# small_laser_supply.net
KiCad netlist of a schematic drawn in EAGLE
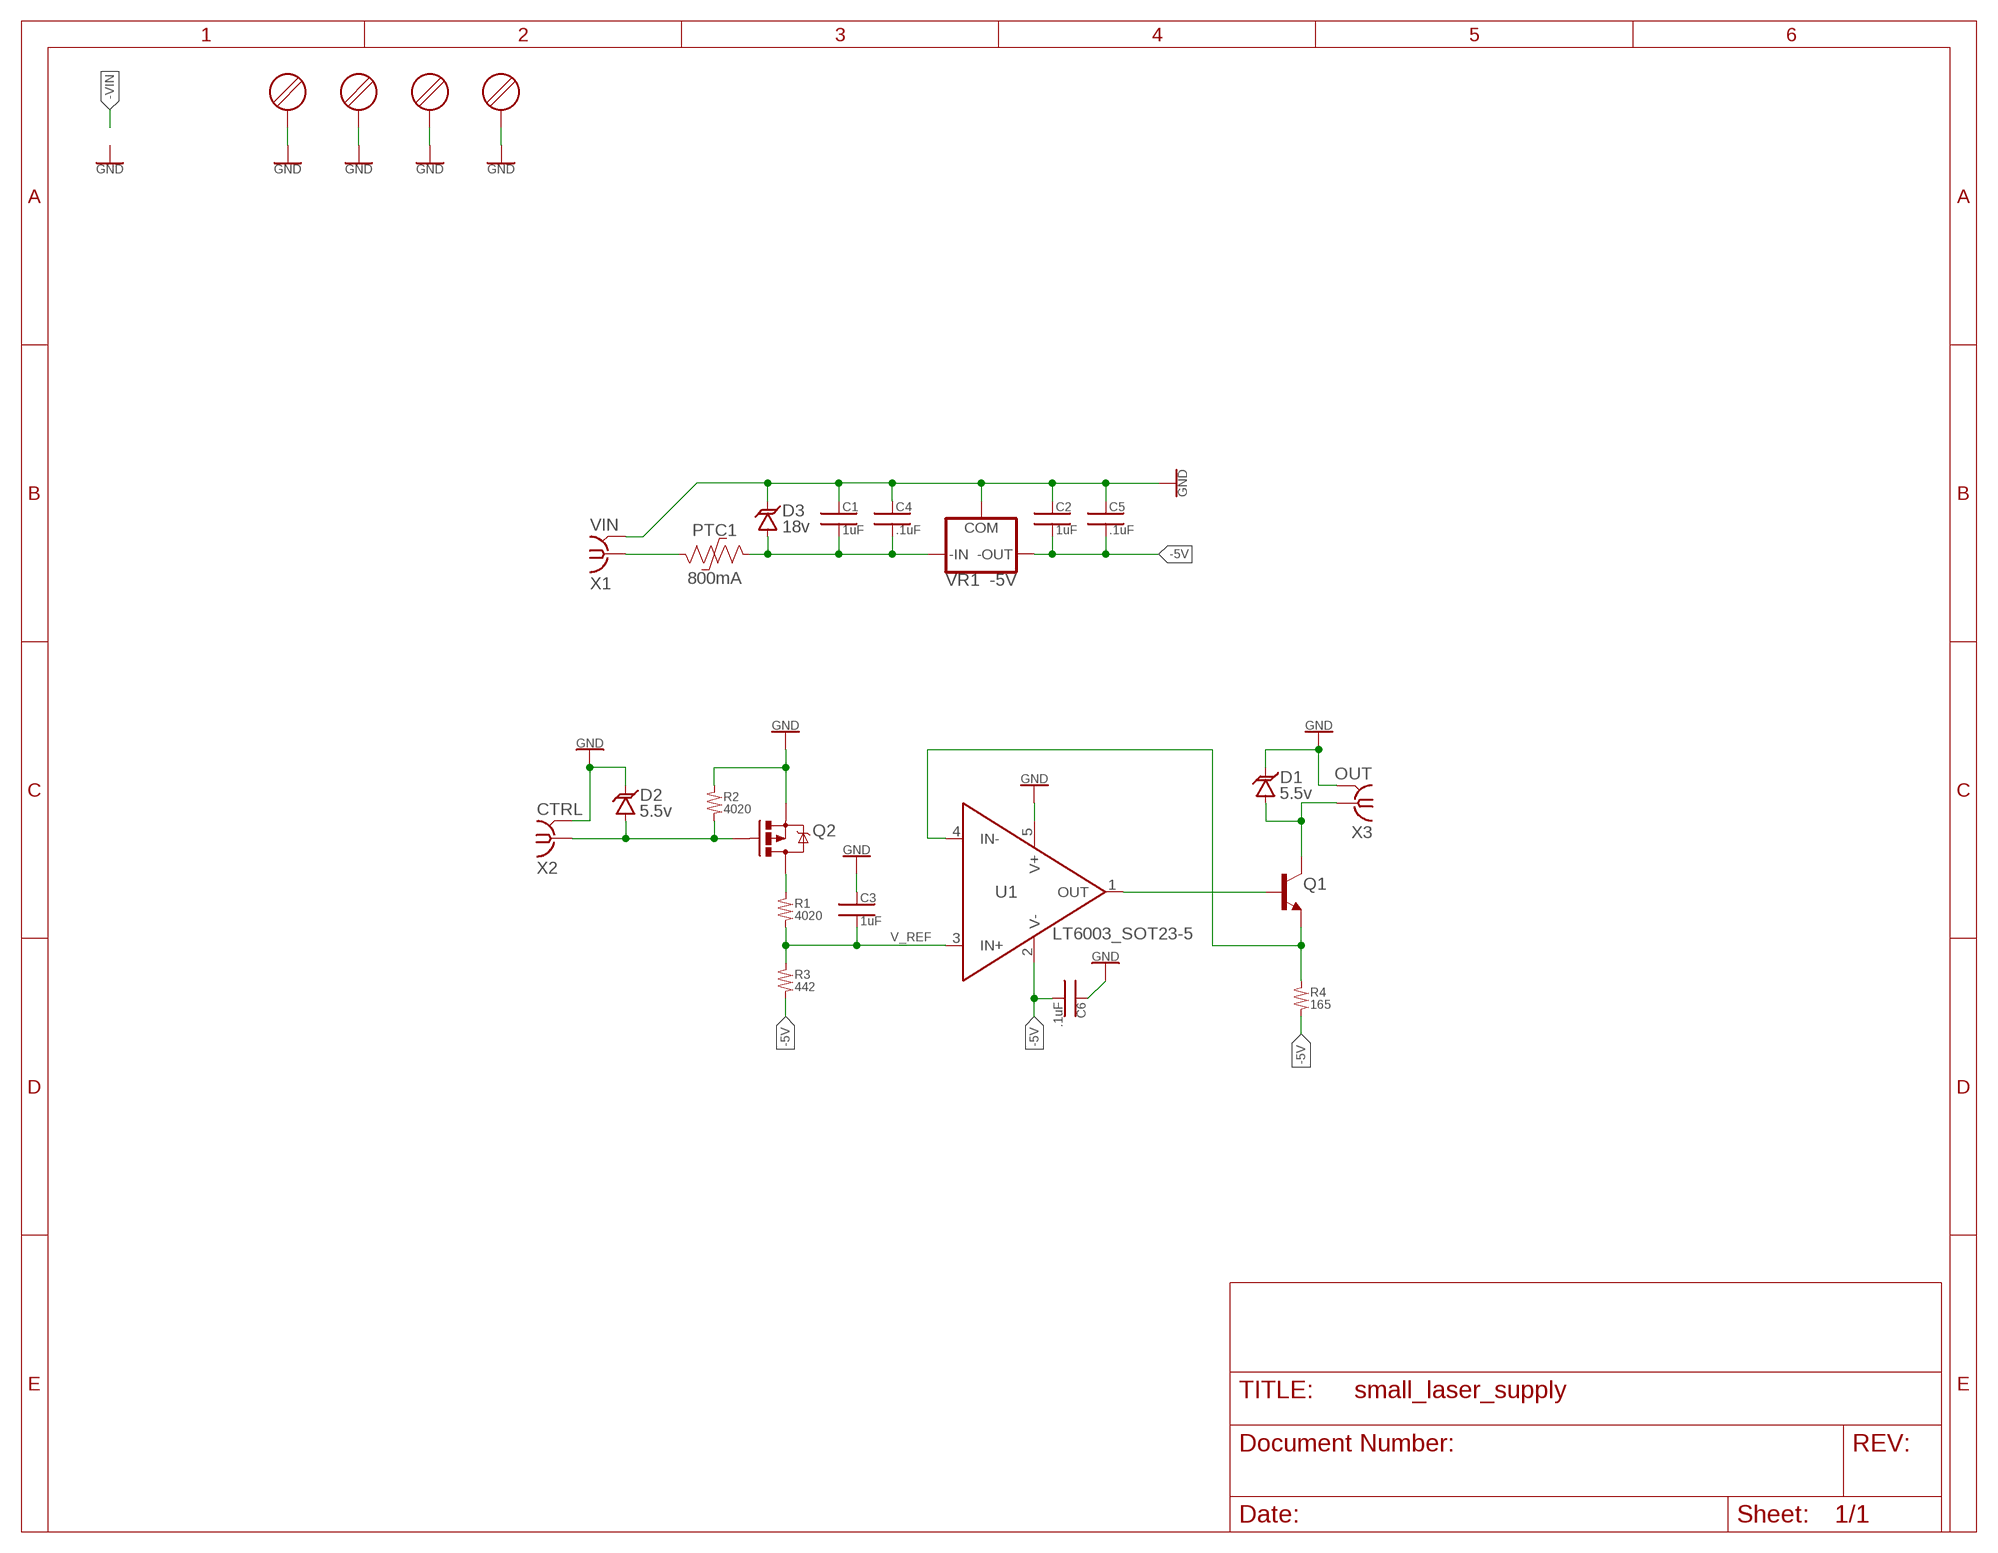
[diagram p0: schematic, sheet 1]

(export (version "E")
  (design (tool "Eeschema 10.0.6"))
  (components
    (comp (ref "C1")
      (value "1uF")
      (footprint "eagle-import:0603")
      (libsource (lib "eagle-import") (part "CAP_0603"))
    )
    (comp (ref "C2")
      (value "1uF")
      (footprint "eagle-import:0603")
      (libsource (lib "eagle-import") (part "CAP_0603"))
    )
    (comp (ref "C3")
      (value "1uF")
      (footprint "eagle-import:0603")
      (libsource (lib "eagle-import") (part "CAP_0603"))
    )
    (comp (ref "C4")
      (value ".1uF")
      (footprint "eagle-import:0603")
      (libsource (lib "eagle-import") (part "CAP_0603"))
    )
    (comp (ref "C5")
      (value ".1uF")
      (footprint "eagle-import:0603")
      (libsource (lib "eagle-import") (part "CAP_0603"))
    )
    (comp (ref "C6")
      (value ".1uF")
      (footprint "eagle-import:0603")
      (libsource (lib "eagle-import") (part "CAP_0603"))
    )
    (comp (ref "D1")
      (value "5.5v")
      (footprint "eagle-import:DO-214AA")
      (libsource (lib "eagle-import") (part "TVS-UNI_DO-214AA"))
    )
    (comp (ref "D2")
      (value "5.5v")
      (footprint "eagle-import:DO-214AA")
      (libsource (lib "eagle-import") (part "TVS-UNI_DO-214AA"))
    )
    (comp (ref "D3")
      (value "18v")
      (footprint "eagle-import:DO-214AA")
      (libsource (lib "eagle-import") (part "TVS-UNI_DO-214AA"))
    )
    (comp (ref "MH1")
      (value "THREADED_INSERT_M3")
      (footprint "eagle-import:7466003R")
      (libsource (lib "eagle-import") (part "THREADED_INSERT_M3"))
    )
    (comp (ref "MH2")
      (value "THREADED_INSERT_M3")
      (footprint "eagle-import:7466003R")
      (libsource (lib "eagle-import") (part "THREADED_INSERT_M3"))
    )
    (comp (ref "MH3")
      (value "THREADED_INSERT_M3")
      (footprint "eagle-import:7466003R")
      (libsource (lib "eagle-import") (part "THREADED_INSERT_M3"))
    )
    (comp (ref "MH4")
      (value "THREADED_INSERT_M3")
      (footprint "eagle-import:7466003R")
      (libsource (lib "eagle-import") (part "THREADED_INSERT_M3"))
    )
    (comp (ref "PTC1")
      (value "800mA")
      (footprint "eagle-import:2SMD_PTC")
      (libsource (lib "eagle-import") (part "PTC_2SMD"))
    )
    (comp (ref "Q1")
      (value "BJT_NPN_SOT23-3")
      (footprint "eagle-import:SOT23-3")
      (libsource (lib "eagle-import") (part "BJT_NPN_SOT23-3"))
    )
    (comp (ref "Q2")
      (value "MOSFET_P-CHANNEL_SOT23-3")
      (footprint "eagle-import:SOT23-3")
      (libsource (lib "eagle-import") (part "MOSFET_P-CHANNEL_SOT23-3"))
    )
    (comp (ref "R1")
      (value "4020")
      (footprint "eagle-import:0603")
      (libsource (lib "eagle-import") (part "RES_0603"))
    )
    (comp (ref "R2")
      (value "4020")
      (footprint "eagle-import:0603")
      (libsource (lib "eagle-import") (part "RES_0603"))
    )
    (comp (ref "R3")
      (value "442")
      (footprint "eagle-import:0603")
      (libsource (lib "eagle-import") (part "RES_0603"))
    )
    (comp (ref "R4")
      (value "165")
      (footprint "eagle-import:0603")
      (libsource (lib "eagle-import") (part "RES_0603"))
    )
    (comp (ref "U1")
      (value "LT6003_SOT23-5")
      (footprint "eagle-import:SOT23-5")
      (libsource (lib "eagle-import") (part "LT6003_SOT23-5"))
    )
    (comp (ref "VR1")
      (value "-5V")
      (footprint "eagle-import:DPAK")
      (libsource (lib "eagle-import") (part "79XX_VREG_DPAK"))
    )
    (comp (ref "X1")
      (value "VIN")
      (footprint "eagle-import:5-1634503-1")
      (libsource (lib "eagle-import") (part "BNC_TE-VERT-PTH"))
    )
    (comp (ref "X2")
      (value "CTRL")
      (footprint "eagle-import:5-1634503-1")
      (libsource (lib "eagle-import") (part "BNC_TE-VERT-PTH"))
    )
    (comp (ref "X3")
      (value "OUT")
      (footprint "eagle-import:5-1634503-1")
      (libsource (lib "eagle-import") (part "BNC_TE-VERT-PTH"))
    )
  )
  (nets
    (net (code "1") (name "-5V") (class "Default")
      (node (ref "C2") (pin "2") (pinfunction "2_2") (pintype "passive"))
      (node (ref "C5") (pin "2") (pinfunction "2_2") (pintype "passive"))
      (node (ref "C6") (pin "2") (pinfunction "2_2") (pintype "passive"))
      (node (ref "R3") (pin "2") (pinfunction "2_2") (pintype "passive"))
      (node (ref "R4") (pin "2") (pinfunction "2_2") (pintype "passive"))
      (node (ref "U1") (pin "2") (pinfunction "V-_2") (pintype "bidirectional"))
      (node (ref "VR1") (pin "3") (pinfunction "OUT_3") (pintype "power_in"))
    )
    (net (code "3") (name "/V_REF") (class "Default")
      (node (ref "C3") (pin "2") (pinfunction "2_2") (pintype "passive"))
      (node (ref "R1") (pin "2") (pinfunction "2_2") (pintype "passive"))
      (node (ref "R3") (pin "1") (pinfunction "1_1") (pintype "passive"))
      (node (ref "U1") (pin "3") (pinfunction "IN+_3") (pintype "bidirectional"))
    )
    (net (code "4") (name "GND") (class "Default")
      (node (ref "C1") (pin "1") (pinfunction "1_1") (pintype "passive"))
      (node (ref "C2") (pin "1") (pinfunction "1_1") (pintype "passive"))
      (node (ref "C3") (pin "1") (pinfunction "1_1") (pintype "passive"))
      (node (ref "C4") (pin "1") (pinfunction "1_1") (pintype "passive"))
      (node (ref "C5") (pin "1") (pinfunction "1_1") (pintype "passive"))
      (node (ref "C6") (pin "1") (pinfunction "1_1") (pintype "passive"))
      (node (ref "D1") (pin "C") (pinfunction "C_C") (pintype "passive"))
      (node (ref "D2") (pin "C") (pinfunction "C_C") (pintype "passive"))
      (node (ref "D3") (pin "C") (pinfunction "C_C") (pintype "passive"))
      (node (ref "MH1") (pin "P") (pinfunction "P_P") (pintype "power_in"))
      (node (ref "MH2") (pin "P") (pinfunction "P_P") (pintype "power_in"))
      (node (ref "MH3") (pin "P") (pinfunction "P_P") (pintype "power_in"))
      (node (ref "MH4") (pin "P") (pinfunction "P_P") (pintype "power_in"))
      (node (ref "Q2") (pin "2") (pinfunction "S_2") (pintype "passive"))
      (node (ref "R2") (pin "1") (pinfunction "1_1") (pintype "passive"))
      (node (ref "U1") (pin "5") (pinfunction "V+_5") (pintype "bidirectional"))
      (node (ref "VR1") (pin "1") (pinfunction "GND_1") (pintype "power_in"))
      (node (ref "X1") (pin "G1") (pinfunction "GND_G1") (pintype "power_in"))
      (node (ref "X1") (pin "G2") (pinfunction "GND_G2") (pintype "power_in"))
      (node (ref "X1") (pin "G3") (pinfunction "GND_G3") (pintype "power_in"))
      (node (ref "X1") (pin "G4") (pinfunction "GND_G4") (pintype "power_in"))
      (node (ref "X2") (pin "G1") (pinfunction "GND_G1") (pintype "power_in"))
      (node (ref "X2") (pin "G2") (pinfunction "GND_G2") (pintype "power_in"))
      (node (ref "X2") (pin "G3") (pinfunction "GND_G3") (pintype "power_in"))
      (node (ref "X2") (pin "G4") (pinfunction "GND_G4") (pintype "power_in"))
      (node (ref "X3") (pin "G1") (pinfunction "GND_G1") (pintype "power_in"))
      (node (ref "X3") (pin "G2") (pinfunction "GND_G2") (pintype "power_in"))
      (node (ref "X3") (pin "G3") (pinfunction "GND_G3") (pintype "power_in"))
      (node (ref "X3") (pin "G4") (pinfunction "GND_G4") (pintype "power_in"))
    )
    (net (code "5") (name "Net-(Q1-B)") (class "Default")
      (node (ref "Q1") (pin "1") (pinfunction "B_1") (pintype "passive"))
      (node (ref "U1") (pin "1") (pinfunction "OUT_1") (pintype "bidirectional"))
    )
    (net (code "6") (name "Net-(Q1-C)") (class "Default")
      (node (ref "D1") (pin "A") (pinfunction "A_A") (pintype "passive"))
      (node (ref "Q1") (pin "3") (pinfunction "C_3") (pintype "passive"))
      (node (ref "X3") (pin "C") (pinfunction "1_C") (pintype "passive"))
    )
    (net (code "7") (name "Net-(Q1-E)") (class "Default")
      (node (ref "Q1") (pin "2") (pinfunction "E_2") (pintype "passive"))
      (node (ref "R4") (pin "1") (pinfunction "1_1") (pintype "passive"))
      (node (ref "U1") (pin "4") (pinfunction "IN-_4") (pintype "bidirectional"))
    )
    (net (code "8") (name "Net-(Q2-D)") (class "Default")
      (node (ref "Q2") (pin "3") (pinfunction "D_3") (pintype "passive"))
      (node (ref "R1") (pin "1") (pinfunction "1_1") (pintype "passive"))
    )
    (net (code "9") (name "Net-(Q2-G)") (class "Default")
      (node (ref "D2") (pin "A") (pinfunction "A_A") (pintype "passive"))
      (node (ref "Q2") (pin "1") (pinfunction "G_1") (pintype "passive"))
      (node (ref "R2") (pin "2") (pinfunction "2_2") (pintype "passive"))
      (node (ref "X2") (pin "C") (pinfunction "1_C") (pintype "passive"))
    )
    (net (code "10") (name "Net-(VR1-IN)") (class "Default")
      (node (ref "C1") (pin "2") (pinfunction "2_2") (pintype "passive"))
      (node (ref "C4") (pin "2") (pinfunction "2_2") (pintype "passive"))
      (node (ref "D3") (pin "A") (pinfunction "A_A") (pintype "passive"))
      (node (ref "PTC1") (pin "2") (pinfunction "2_2") (pintype "power_in"))
      (node (ref "VR1") (pin "4") (pinfunction "IN_4") (pintype "power_in"))
    )
    (net (code "11") (name "Net-(X1-1)") (class "Default")
      (node (ref "PTC1") (pin "1") (pinfunction "1_1") (pintype "power_in"))
      (node (ref "X1") (pin "C") (pinfunction "1_C") (pintype "passive"))
    )
  )
)
